# ServoMotCTRL.net
KiCad netlist of a schematic drawn in Altium Designer
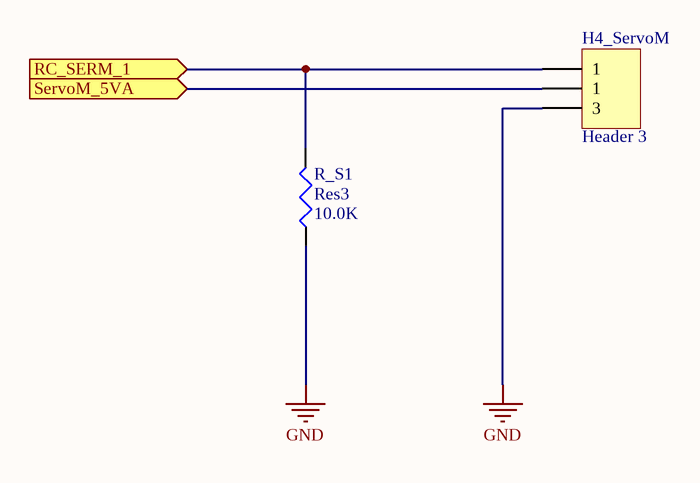
[diagram p0: ServoMotCTRL.SchDoc]

(export (version "E")
  (design (tool "Eeschema 10.0.6"))
  (components
    (comp (ref "H4_ServoM")
      (value "Header 3")
      (footprint "HDR1X3")
      (description "Header, 3-Pin")
      (fields (field (name "PUBLISHER") "Altium Limited"))
      (libsource (lib "Miscellaneous Connectors") (part "Header 3"))
    )
    (comp (ref "R_S1")
      (value "Res3")
      (footprint "RESC2112X05M")
      (description "RES SMD 10.0K OHM 1% 1/8W 0805")
      (fields (field (name "ALTIUM_VALUE") "10.0K") (field (name "MPN") "CRCW080510K0FKEA"))
      (libsource (lib "esd_library") (part "Resistor_10.0K"))
    )
  )
  (nets
    (net (code "1") (name "/RC_SERM_1") (class "Default")
      (node (ref "H4_ServoM") (pin "1") (pinfunction "1_1") (pintype "passive"))
      (node (ref "R_S1") (pin "2") (pinfunction "2_2") (pintype "passive"))
    )
    (net (code "2") (name "/ServoM_5VA") (class "Default")
      (node (ref "H4_ServoM") (pin "1") (pinfunction "1_1") (pintype "passive"))
    )
    (net (code "3") (name "GND") (class "Default")
      (node (ref "H4_ServoM") (pin "3") (pinfunction "3_3") (pintype "passive"))
      (node (ref "R_S1") (pin "1") (pinfunction "1_1") (pintype "passive"))
    )
  )
)
